# EtherCATConnectors.net
KiCad netlist of a schematic drawn in Altium Designer
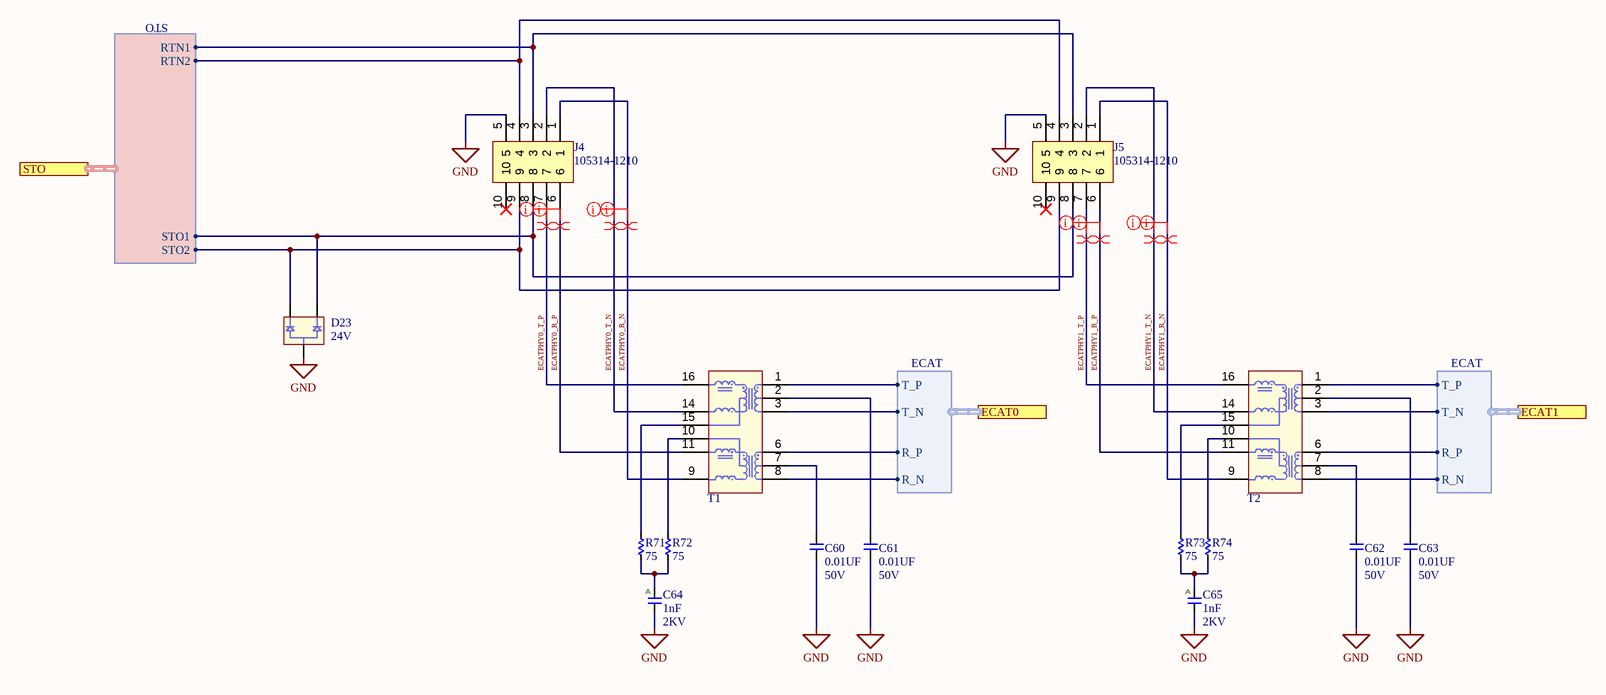
[diagram p0: EtherCATConnectors.SchDoc]

(export (version "E")
  (design (tool "Eeschema 10.0.6"))
  (components
    (comp (ref "C60")
      (value "0.01UF")
      (footprint "C0402")
      (description "CAP, CER, X7R, 0.01uF, 50V, 20%, 0402, 0.56mm T")
      (fields (field (name "MFG") "KEMET") (field (name "VOLTAGE") "50V") (field (name "TOLERANCE") "20%"))
      (libsource (lib "AltiumReleaseLibDB") (part "__Template_Cap"))
    )
    (comp (ref "C61")
      (value "0.01UF")
      (footprint "C0402")
      (description "CAP, CER, X7R, 0.01uF, 50V, 20%, 0402, 0.56mm T")
      (fields (field (name "MFG") "KEMET") (field (name "VOLTAGE") "50V") (field (name "TOLERANCE") "20%"))
      (libsource (lib "AltiumReleaseLibDB") (part "__Template_Cap"))
    )
    (comp (ref "C62")
      (value "0.01UF")
      (footprint "C0402")
      (description "CAP, CER, X7R, 0.01uF, 50V, 20%, 0402, 0.56mm T")
      (fields (field (name "MFG") "KEMET") (field (name "VOLTAGE") "50V") (field (name "TOLERANCE") "20%"))
      (libsource (lib "AltiumReleaseLibDB") (part "__Template_Cap"))
    )
    (comp (ref "C63")
      (value "0.01UF")
      (footprint "C0402")
      (description "CAP, CER, X7R, 0.01uF, 50V, 20%, 0402, 0.56mm T")
      (fields (field (name "MFG") "KEMET") (field (name "VOLTAGE") "50V") (field (name "TOLERANCE") "20%"))
      (libsource (lib "AltiumReleaseLibDB") (part "__Template_Cap"))
    )
    (comp (ref "C64")
      (value "1nF")
      (footprint "C1210")
      (description "CAP, CER, X7S, 1000PF, 2KV, 10%, 1210")
      (fields (field (name "MFG") "TDK") (field (name "VOLTAGE") "2KV") (field (name "TOLERANCE") "10%"))
      (libsource (lib "AltiumReleaseLibDB") (part "__Template_Cap_Auto"))
    )
    (comp (ref "C65")
      (value "1nF")
      (footprint "C1210")
      (description "CAP, CER, X7S, 1000PF, 2KV, 10%, 1210")
      (fields (field (name "MFG") "TDK") (field (name "VOLTAGE") "2KV") (field (name "TOLERANCE") "10%"))
      (libsource (lib "AltiumReleaseLibDB") (part "__Template_Cap_Auto"))
    )
    (comp (ref "D23")
      (value "24V")
      (footprint "3SOT23")
      (description "DIODE, TVS, UNIDIR, DUAL, 24VRWM, 26VBR, 41VCL, SOT-23-3")
      (fields (field (name "MFG") "Infineon Technologies"))
      (libsource (lib "AltiumReleaseLibDB") (part "DIODE_TVS_ESD24VS2UE6327HTSA1"))
    )
    (comp (ref "J4")
      (value "MOLEX_2X5_NANOFIT_1053141210")
      (footprint "MOLEX_1053141210")
      (description "Conn HDR 10 POS 2.5mm Solder RA Thru-Hole 10 Terminal 1 Port")
      (fields (field (name "MANUFACTURER") "Molex") (field (name "MANUFACTURER PART NUMBER") "105314-1210"))
      (libsource (lib "MiscSch1") (part "MOLEX_2X5_NANOFIT_1053141210"))
    )
    (comp (ref "J5")
      (value "MOLEX_2X5_NANOFIT_1053141210")
      (footprint "MOLEX_1053141210")
      (description "Conn HDR 10 POS 2.5mm Solder RA Thru-Hole 10 Terminal 1 Port")
      (fields (field (name "MANUFACTURER") "Molex") (field (name "MANUFACTURER PART NUMBER") "105314-1210"))
      (libsource (lib "MiscSch1") (part "MOLEX_2X5_NANOFIT_1053141210"))
    )
    (comp (ref "R71")
      (value "75")
      (footprint "R0402")
      (description "RES, 75, 1%, 1/16W, 0402")
      (fields (field (name "MFG") "YAGEO") (field (name "POWER") "1/16W"))
      (libsource (lib "AltiumReleaseLibDB") (part "__Template_Resistor"))
    )
    (comp (ref "R72")
      (value "75")
      (footprint "R0402")
      (description "RES, 75, 1%, 1/16W, 0402")
      (fields (field (name "MFG") "YAGEO") (field (name "POWER") "1/16W"))
      (libsource (lib "AltiumReleaseLibDB") (part "__Template_Resistor"))
    )
    (comp (ref "R73")
      (value "75")
      (footprint "R0402")
      (description "RES, 75, 1%, 1/16W, 0402")
      (fields (field (name "MFG") "YAGEO") (field (name "POWER") "1/16W"))
      (libsource (lib "AltiumReleaseLibDB") (part "__Template_Resistor"))
    )
    (comp (ref "R74")
      (value "75")
      (footprint "R0402")
      (description "RES, 75, 1%, 1/16W, 0402")
      (fields (field (name "MFG") "YAGEO") (field (name "POWER") "1/16W"))
      (libsource (lib "AltiumReleaseLibDB") (part "__Template_Resistor"))
    )
    (comp (ref "T1")
      (value "PULSE_H1102NL")
      (footprint "PULSE_HXXXX")
      (description "Telecom Transformer 2(1:1) 0.65Ohm Prim. DCR 0.65Ohm Sec. DCR 16 Terminal Gull Wing SMD")
      (fields (field (name "MANUFACTURER") "Pulse") (field (name "MANUFACTURER PART NUMBER") "H1102NL"))
      (libsource (lib "MiscSch1") (part "PULSE_H1102NL"))
    )
    (comp (ref "T2")
      (value "PULSE_H1102NL")
      (footprint "PULSE_HXXXX")
      (description "Telecom Transformer 2(1:1) 0.65Ohm Prim. DCR 0.65Ohm Sec. DCR 16 Terminal Gull Wing SMD")
      (fields (field (name "MANUFACTURER") "Pulse") (field (name "MANUFACTURER PART NUMBER") "H1102NL"))
      (libsource (lib "MiscSch1") (part "PULSE_H1102NL"))
    )
  )
  (nets
    (net (code "3") (name "/ECATPHY0_R_N") (class "Default")
      (node (ref "J4") (pin "1") (pinfunction "1_1") (pintype "passive"))
      (node (ref "T1") (pin "9") (pintype "passive"))
    )
    (net (code "4") (name "/ECATPHY0_R_P") (class "Default")
      (node (ref "J4") (pin "6") (pinfunction "6_6") (pintype "passive"))
      (node (ref "T1") (pin "11") (pintype "passive"))
    )
    (net (code "5") (name "/ECATPHY0_T_N") (class "Default")
      (node (ref "J4") (pin "2") (pinfunction "2_2") (pintype "passive"))
      (node (ref "T1") (pin "14") (pintype "passive"))
    )
    (net (code "6") (name "/ECATPHY0_T_P") (class "Default")
      (node (ref "J4") (pin "7") (pinfunction "7_7") (pintype "passive"))
      (node (ref "T1") (pin "16") (pintype "passive"))
    )
    (net (code "7") (name "/ECATPHY1_R_N") (class "Default")
      (node (ref "J5") (pin "1") (pinfunction "1_1") (pintype "passive"))
      (node (ref "T2") (pin "9") (pintype "passive"))
    )
    (net (code "8") (name "/ECATPHY1_R_P") (class "Default")
      (node (ref "J5") (pin "6") (pinfunction "6_6") (pintype "passive"))
      (node (ref "T2") (pin "11") (pintype "passive"))
    )
    (net (code "9") (name "/ECATPHY1_T_N") (class "Default")
      (node (ref "J5") (pin "2") (pinfunction "2_2") (pintype "passive"))
      (node (ref "T2") (pin "14") (pintype "passive"))
    )
    (net (code "10") (name "/ECATPHY1_T_P") (class "Default")
      (node (ref "J5") (pin "7") (pinfunction "7_7") (pintype "passive"))
      (node (ref "T2") (pin "16") (pintype "passive"))
    )
    (net (code "11") (name "/RTN1") (class "Default")
      (node (ref "J4") (pin "3") (pinfunction "3_3") (pintype "passive"))
      (node (ref "J5") (pin "3") (pinfunction "3_3") (pintype "passive"))
    )
    (net (code "12") (name "/RTN2") (class "Default")
      (node (ref "J4") (pin "4") (pinfunction "4_4") (pintype "passive"))
      (node (ref "J5") (pin "4") (pinfunction "4_4") (pintype "passive"))
    )
    (net (code "13") (name "/STO1") (class "Default")
      (node (ref "D23") (pin "1") (pinfunction "1_1") (pintype "passive"))
      (node (ref "J4") (pin "8") (pinfunction "8_8") (pintype "passive"))
      (node (ref "J5") (pin "8") (pinfunction "8_8") (pintype "passive"))
    )
    (net (code "14") (name "/STO2") (class "Default")
      (node (ref "D23") (pin "2") (pinfunction "2_2") (pintype "passive"))
      (node (ref "J4") (pin "9") (pinfunction "9_9") (pintype "passive"))
      (node (ref "J5") (pin "9") (pinfunction "9_9") (pintype "passive"))
    )
    (net (code "17") (name "GND") (class "Default")
      (node (ref "C60") (pin "2") (pintype "passive"))
      (node (ref "C61") (pin "2") (pintype "passive"))
      (node (ref "C62") (pin "2") (pintype "passive"))
      (node (ref "C63") (pin "2") (pintype "passive"))
      (node (ref "C64") (pin "2") (pintype "passive"))
      (node (ref "C65") (pin "2") (pintype "passive"))
      (node (ref "D23") (pin "3") (pinfunction "3_3") (pintype "passive"))
      (node (ref "J4") (pin "5") (pinfunction "5_5") (pintype "passive"))
      (node (ref "J5") (pin "5") (pinfunction "5_5") (pintype "passive"))
    )
    (net (code "18") (name "Net-(C60-Pad1)") (class "Default")
      (node (ref "C60") (pin "1") (pintype "passive"))
      (node (ref "T1") (pin "7") (pintype "passive"))
    )
    (net (code "19") (name "Net-(C61-Pad1)") (class "Default")
      (node (ref "C61") (pin "1") (pintype "passive"))
      (node (ref "T1") (pin "2") (pintype "passive"))
    )
    (net (code "20") (name "Net-(C62-Pad1)") (class "Default")
      (node (ref "C62") (pin "1") (pintype "passive"))
      (node (ref "T2") (pin "7") (pintype "passive"))
    )
    (net (code "21") (name "Net-(C63-Pad1)") (class "Default")
      (node (ref "C63") (pin "1") (pintype "passive"))
      (node (ref "T2") (pin "2") (pintype "passive"))
    )
    (net (code "22") (name "Net-(C64-Pad1)") (class "Default")
      (node (ref "C64") (pin "1") (pintype "passive"))
      (node (ref "R71") (pin "1") (pintype "passive"))
      (node (ref "R72") (pin "1") (pintype "passive"))
    )
    (net (code "23") (name "Net-(C65-Pad1)") (class "Default")
      (node (ref "C65") (pin "1") (pintype "passive"))
      (node (ref "R73") (pin "1") (pintype "passive"))
      (node (ref "R74") (pin "1") (pintype "passive"))
    )
    (net (code "24") (name "Net-(R71-Pad2)") (class "Default")
      (node (ref "R71") (pin "2") (pintype "passive"))
      (node (ref "T1") (pin "15") (pintype "passive"))
    )
    (net (code "25") (name "Net-(R72-Pad2)") (class "Default")
      (node (ref "R72") (pin "2") (pintype "passive"))
      (node (ref "T1") (pin "10") (pintype "passive"))
    )
    (net (code "26") (name "Net-(R73-Pad2)") (class "Default")
      (node (ref "R73") (pin "2") (pintype "passive"))
      (node (ref "T2") (pin "15") (pintype "passive"))
    )
    (net (code "27") (name "Net-(R74-Pad2)") (class "Default")
      (node (ref "R74") (pin "2") (pintype "passive"))
      (node (ref "T2") (pin "10") (pintype "passive"))
    )
    (net (code "28") (name "unconnected-(J4-Pad10)") (class "Default")
      (node (ref "J4") (pin "10") (pinfunction "10_10") (pintype "passive+no_connect"))
    )
    (net (code "29") (name "unconnected-(J5-Pad10)") (class "Default")
      (node (ref "J5") (pin "10") (pinfunction "10_10") (pintype "passive+no_connect"))
    )
    (net (code "30") (name "unconnected-(T1-Pad1)") (class "Default")
      (node (ref "T1") (pin "1") (pintype "passive"))
    )
    (net (code "31") (name "unconnected-(T1-Pad3)") (class "Default")
      (node (ref "T1") (pin "3") (pintype "passive"))
    )
    (net (code "32") (name "unconnected-(T1-Pad6)") (class "Default")
      (node (ref "T1") (pin "6") (pintype "passive"))
    )
    (net (code "33") (name "unconnected-(T1-Pad8)") (class "Default")
      (node (ref "T1") (pin "8") (pintype "passive"))
    )
    (net (code "34") (name "unconnected-(T2-Pad1)") (class "Default")
      (node (ref "T2") (pin "1") (pintype "passive"))
    )
    (net (code "35") (name "unconnected-(T2-Pad3)") (class "Default")
      (node (ref "T2") (pin "3") (pintype "passive"))
    )
    (net (code "36") (name "unconnected-(T2-Pad6)") (class "Default")
      (node (ref "T2") (pin "6") (pintype "passive"))
    )
    (net (code "37") (name "unconnected-(T2-Pad8)") (class "Default")
      (node (ref "T2") (pin "8") (pintype "passive"))
    )
  )
)
